# EbookReader_Schematic.net
KiCad netlist of a schematic drawn in EAGLE
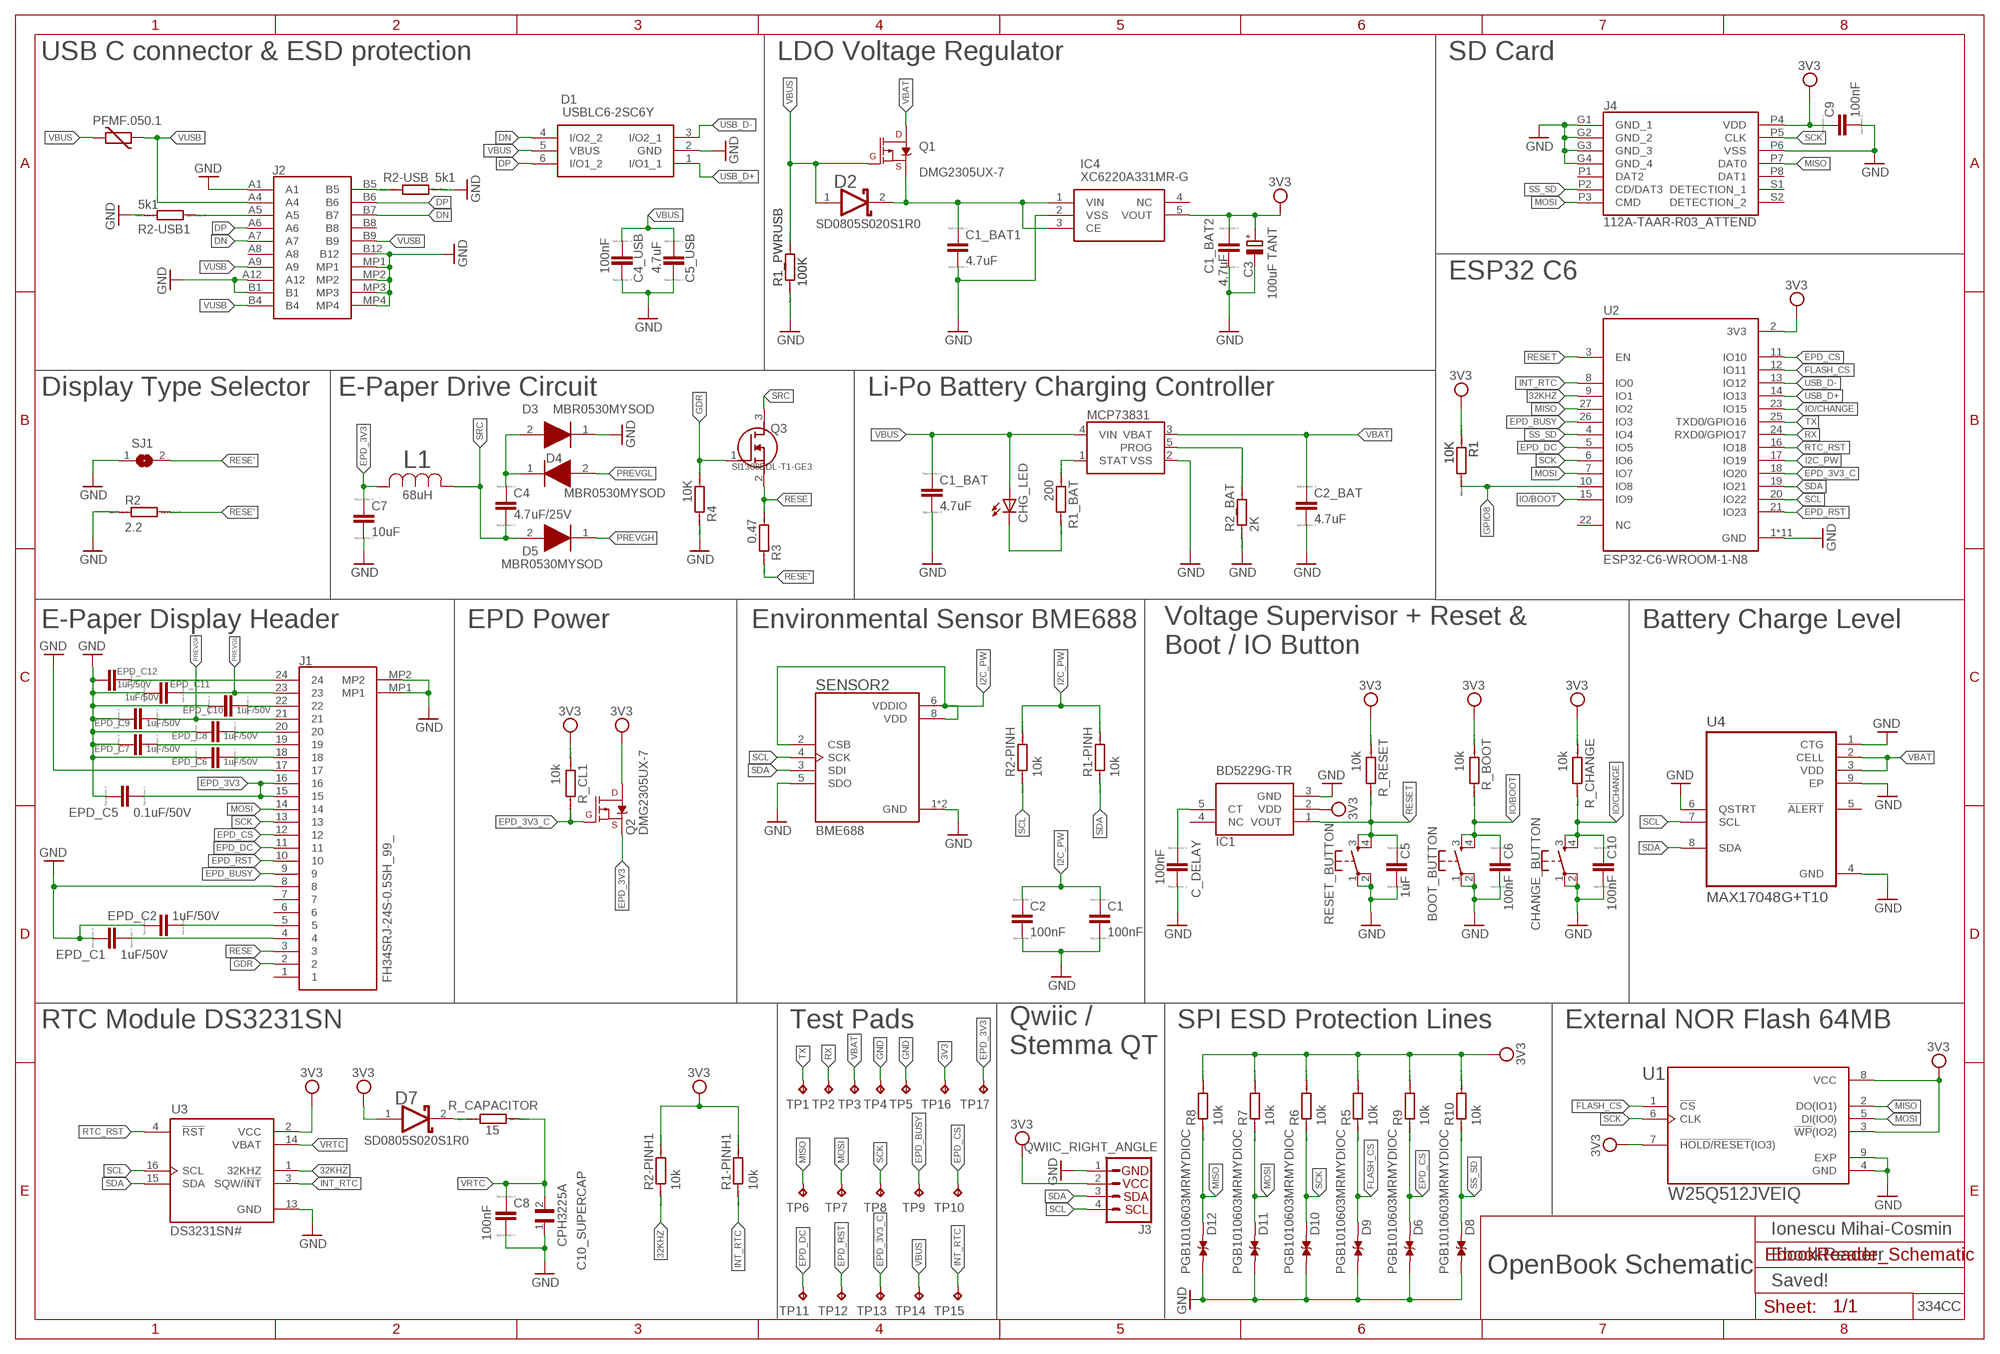
[diagram p0: schematic, sheet 1]

(export (version "E")
  (design (tool "Eeschema 10.0.6"))
  (components
    (comp (ref "BOOT_BUTTON")
      (value "BUTTON_CUSYOMV1FINAL_BUTT")
      (footprint "eagle-import:MYBUTTON")
      (libsource (lib "eagle-import") (part "BUTTON_CUSYOMV1FINAL_BUTT"))
    )
    (comp (ref "C1")
      (value "100nF")
      (footprint "eagle-import:EAGLE-LTSPICE_C0402")
      (libsource (lib "eagle-import") (part "ESP32_WROVER_EAGLE-LTSPICE_C"))
    )
    (comp (ref "C1_BAT")
      (value "4.7uF")
      (footprint "eagle-import:EAGLE-LTSPICE_C0402")
      (libsource (lib "eagle-import") (part "ESP32_WROVER_EAGLE-LTSPICE_C"))
    )
    (comp (ref "C1_BAT1")
      (value "4.7uF")
      (footprint "eagle-import:EAGLE-LTSPICE_C0402")
      (libsource (lib "eagle-import") (part "ESP32_WROVER_EAGLE-LTSPICE_C"))
    )
    (comp (ref "C1_BAT2")
      (value "4.7uF")
      (footprint "eagle-import:EAGLE-LTSPICE_C0402")
      (libsource (lib "eagle-import") (part "ESP32_WROVER_EAGLE-LTSPICE_C"))
    )
    (comp (ref "C2")
      (value "100nF")
      (footprint "eagle-import:EAGLE-LTSPICE_C0402")
      (libsource (lib "eagle-import") (part "ESP32_WROVER_EAGLE-LTSPICE_C"))
    )
    (comp (ref "C2_BAT")
      (value "4.7uF")
      (footprint "eagle-import:EAGLE-LTSPICE_C0402")
      (libsource (lib "eagle-import") (part "ESP32_WROVER_EAGLE-LTSPICE_C"))
    )
    (comp (ref "C3")
      (value "100uF TANT")
      (footprint "eagle-import:RCL_CT3528")
      (libsource (lib "eagle-import") (part "RCL_CPOL-EUCT3528"))
    )
    (comp (ref "C4")
      (value "4.7uF/25V")
      (footprint "eagle-import:EAGLE-LTSPICE_C0402")
      (libsource (lib "eagle-import") (part "ESP32_WROVER_EAGLE-LTSPICE_C"))
    )
    (comp (ref "C4_USB")
      (value "100nF")
      (footprint "eagle-import:EAGLE-LTSPICE_C0402")
      (libsource (lib "eagle-import") (part "ESP32_WROVER_EAGLE-LTSPICE_C"))
    )
    (comp (ref "C5")
      (value "1uF")
      (footprint "eagle-import:EAGLE-LTSPICE_C0402")
      (libsource (lib "eagle-import") (part "ESP32_WROVER_EAGLE-LTSPICE_C"))
    )
    (comp (ref "C5_USB")
      (value "4.7uF")
      (footprint "eagle-import:EAGLE-LTSPICE_C0402")
      (libsource (lib "eagle-import") (part "ESP32_WROVER_EAGLE-LTSPICE_C"))
    )
    (comp (ref "C6")
      (value "100nF")
      (footprint "eagle-import:EAGLE-LTSPICE_C0402")
      (libsource (lib "eagle-import") (part "ESP32_WROVER_EAGLE-LTSPICE_C"))
    )
    (comp (ref "C7")
      (value "10uF")
      (footprint "eagle-import:EAGLE-LTSPICE_C0402")
      (libsource (lib "eagle-import") (part "ESP32_WROVER_EAGLE-LTSPICE_C"))
    )
    (comp (ref "C8")
      (value "100nF")
      (footprint "eagle-import:EAGLE-LTSPICE_C0402")
      (libsource (lib "eagle-import") (part "ESP32_WROVER_EAGLE-LTSPICE_C"))
    )
    (comp (ref "C9")
      (value "100nF")
      (footprint "eagle-import:EAGLE-LTSPICE_C0402")
      (libsource (lib "eagle-import") (part "ESP32_WROVER_EAGLE-LTSPICE_C"))
    )
    (comp (ref "C10")
      (value "100nF")
      (footprint "eagle-import:EAGLE-LTSPICE_C0402")
      (libsource (lib "eagle-import") (part "ESP32_WROVER_EAGLE-LTSPICE_C"))
    )
    (comp (ref "C10_SUPERCAP")
      (value "CPH3225A")
      (footprint "eagle-import:CAPCP3225X100N")
      (fields (field (name "MF") "Seiko Instruments"))
      (libsource (lib "eagle-import") (part "CPH3225A"))
    )
    (comp (ref "CHANGE_BUTTON")
      (value "BUTTON_CUSYOMV1FINAL_BUTT")
      (footprint "eagle-import:MYBUTTON")
      (libsource (lib "eagle-import") (part "BUTTON_CUSYOMV1FINAL_BUTT"))
    )
    (comp (ref "CHG_LED")
      (value "ADAFRUIT_LEDCHIP-LED0603")
      (footprint "eagle-import:ADAFRUIT_CHIP-LED0603")
      (libsource (lib "eagle-import") (part "ADAFRUIT_LEDCHIP-LED0603"))
    )
    (comp (ref "C_DELAY")
      (value "100nF")
      (footprint "eagle-import:EAGLE-LTSPICE_C0402")
      (libsource (lib "eagle-import") (part "ESP32_WROVER_EAGLE-LTSPICE_C"))
    )
    (comp (ref "D1")
      (value "USBLC6-2SC6Y")
      (footprint "eagle-import:SOT95P280X145-6N")
      (fields (field (name "MF") "STMicroelectronics"))
      (libsource (lib "eagle-import") (part "USBLC6-2SC6Y"))
    )
    (comp (ref "D2")
      (value "ESP32_WROVER_AVX---SD0805S020S1R0_AVX_SD0805S020S1R0_0_0")
      (footprint "eagle-import:ESP32_WROVER_AVX---SD0805S020S1R0_AVX_SD0805S020S1R0_0")
      (fields (field (name "FOOPRINT") "SD0805S020S1R0"))
      (libsource (lib "eagle-import") (part "ESP32_WROVER_AVX---SD0805S020S1R0_AVX_SD0805S020S1R0_0_0"))
    )
    (comp (ref "D3")
      (value "MBR0530MYSOD")
      (footprint "eagle-import:SOD3716X135N")
      (libsource (lib "eagle-import") (part "MBR0530MYSOD"))
    )
    (comp (ref "D4")
      (value "MBR0530MYSOD")
      (footprint "eagle-import:SOD3716X135N")
      (libsource (lib "eagle-import") (part "MBR0530MYSOD"))
    )
    (comp (ref "D5")
      (value "MBR0530MYSOD")
      (footprint "eagle-import:SOD3716X135N")
      (libsource (lib "eagle-import") (part "MBR0530MYSOD"))
    )
    (comp (ref "D6")
      (value "PGB1010603MRMYDIOC")
      (footprint "eagle-import:DIOC1608X36N")
      (libsource (lib "eagle-import") (part "PGB1010603MRMYDIOC"))
    )
    (comp (ref "D7")
      (value "ESP32_WROVER_AVX---SD0805S020S1R0_AVX_SD0805S020S1R0_0_0")
      (footprint "eagle-import:ESP32_WROVER_AVX---SD0805S020S1R0_AVX_SD0805S020S1R0_0")
      (fields (field (name "FOOPRINT") "SD0805S020S1R0"))
      (libsource (lib "eagle-import") (part "ESP32_WROVER_AVX---SD0805S020S1R0_AVX_SD0805S020S1R0_0_0"))
    )
    (comp (ref "D8")
      (value "PGB1010603MRMYDIOC")
      (footprint "eagle-import:DIOC1608X36N")
      (libsource (lib "eagle-import") (part "PGB1010603MRMYDIOC"))
    )
    (comp (ref "D9")
      (value "PGB1010603MRMYDIOC")
      (footprint "eagle-import:DIOC1608X36N")
      (libsource (lib "eagle-import") (part "PGB1010603MRMYDIOC"))
    )
    (comp (ref "D10")
      (value "PGB1010603MRMYDIOC")
      (footprint "eagle-import:DIOC1608X36N")
      (libsource (lib "eagle-import") (part "PGB1010603MRMYDIOC"))
    )
    (comp (ref "D11")
      (value "PGB1010603MRMYDIOC")
      (footprint "eagle-import:DIOC1608X36N")
      (libsource (lib "eagle-import") (part "PGB1010603MRMYDIOC"))
    )
    (comp (ref "D12")
      (value "PGB1010603MRMYDIOC")
      (footprint "eagle-import:DIOC1608X36N")
      (libsource (lib "eagle-import") (part "PGB1010603MRMYDIOC"))
    )
    (comp (ref "EPD_C1")
      (value "1uF/50V")
      (footprint "eagle-import:EAGLE-LTSPICE_C0402")
      (libsource (lib "eagle-import") (part "ESP32_WROVER_EAGLE-LTSPICE_C"))
    )
    (comp (ref "EPD_C2")
      (value "1uF/50V")
      (footprint "eagle-import:EAGLE-LTSPICE_C0402")
      (libsource (lib "eagle-import") (part "ESP32_WROVER_EAGLE-LTSPICE_C"))
    )
    (comp (ref "EPD_C5")
      (value "0.1uF/50V")
      (footprint "eagle-import:EAGLE-LTSPICE_C0402")
      (libsource (lib "eagle-import") (part "ESP32_WROVER_EAGLE-LTSPICE_C"))
    )
    (comp (ref "EPD_C6")
      (value "1uF/50V")
      (footprint "eagle-import:EAGLE-LTSPICE_C0402")
      (libsource (lib "eagle-import") (part "ESP32_WROVER_EAGLE-LTSPICE_C"))
    )
    (comp (ref "EPD_C7")
      (value "1uF/50V")
      (footprint "eagle-import:EAGLE-LTSPICE_C0402")
      (libsource (lib "eagle-import") (part "ESP32_WROVER_EAGLE-LTSPICE_C"))
    )
    (comp (ref "EPD_C8")
      (value "1uF/50V")
      (footprint "eagle-import:EAGLE-LTSPICE_C0402")
      (libsource (lib "eagle-import") (part "ESP32_WROVER_EAGLE-LTSPICE_C"))
    )
    (comp (ref "EPD_C9")
      (value "1uF/50V")
      (footprint "eagle-import:EAGLE-LTSPICE_C0402")
      (libsource (lib "eagle-import") (part "ESP32_WROVER_EAGLE-LTSPICE_C"))
    )
    (comp (ref "EPD_C10")
      (value "1uF/50V")
      (footprint "eagle-import:EAGLE-LTSPICE_C0402")
      (libsource (lib "eagle-import") (part "ESP32_WROVER_EAGLE-LTSPICE_C"))
    )
    (comp (ref "EPD_C11")
      (value "1uF/50V")
      (footprint "eagle-import:EAGLE-LTSPICE_C0402")
      (libsource (lib "eagle-import") (part "ESP32_WROVER_EAGLE-LTSPICE_C"))
    )
    (comp (ref "EPD_C12")
      (value "1uF/50V")
      (footprint "eagle-import:EAGLE-LTSPICE_C0402")
      (libsource (lib "eagle-import") (part "ESP32_WROVER_EAGLE-LTSPICE_C"))
    )
    (comp (ref "IC1")
      (value "BD5229G-TR")
      (footprint "eagle-import:SOT95P280X125-5N")
      (fields (field (name "MOUSER_PART_NUMBER") "755-BD5229G-TR"))
      (libsource (lib "eagle-import") (part "BD5229G-TR"))
    )
    (comp (ref "IC4")
      (value "XC6220A331MR-G")
      (footprint "eagle-import:SOT95P280X120-5N")
      (fields (field (name "MOUSER_PART_NUMBER") "865-XC6220A331MR-G"))
      (libsource (lib "eagle-import") (part "XC6220A331MR-G"))
    )
    (comp (ref "J1")
      (value "FH34SRJ-24S-0.5SH_99_")
      (footprint "eagle-import:FH34SRJ24S05SH99")
      (fields
        (field (name "MANUFACTURER_PART_NUMBER") "FH34SRJ-24S-0.5SH(99)")
        (field (name "MOUSER_PART_NUMBER") "798-FH34SRJ24S05SH99")
      )
      (libsource (lib "eagle-import") (part "FH34SRJ-24S-0.5SH_99_"))
    )
    (comp (ref "J2")
      (value "SAMACSYS_PARTS_USB4110-GF-A")
      (footprint "eagle-import:SAMACSYS_PARTS_USB4110GFA")
      (fields
        (field (name "MANUFACTURER_PART_NUMBER") "USB4110-GF-A")
        (field (name "MOUSER_PART_NUMBER") "640-USB4110-GF-A")
      )
      (libsource (lib "eagle-import") (part "SAMACSYS_PARTS_USB4110-GF-A"))
    )
    (comp (ref "J3")
      (value "QWIIC_RIGHT_ANGLE")
      (footprint "eagle-import:JST04_1MM_RA")
      (libsource (lib "eagle-import") (part "QWIIC_CONNECTORJS-1MM"))
    )
    (comp (ref "J4")
      (value "112A-TAAR-R03_ATTEND")
      (footprint "eagle-import:112ATAARR03ATTEND")
      (fields (field (name "MANUFACTURER_PART_NUMBER") "112A-TAAR-R03 ATTEND"))
      (libsource (lib "eagle-import") (part "112A-TAAR-R03_ATTEND"))
    )
    (comp (ref "L1")
      (value "744043680IND_4828-WE-TPC_WRE")
      (footprint "eagle-import:IND_4828-WE-TPC_WRE")
      (fields
        (field (name "MANUFACTURER_PART_NUMBER") "744043680")
        (field (name "VAL") "68uH")
        (field (name "COPYRIGHT") "Copyright (C) 2024 Ultra Librarian. All rights reserved.")
      )
      (libsource (lib "eagle-import") (part "744043680IND_4828-WE-TPC_WRE"))
    )
    (comp (ref "MCP73831")
      (value "ESP32_WROVER_SPARKFUN-IC-POWER_MCP73831")
      (footprint "eagle-import:ESP32_WROVER_SPARKFUN-IC-POWER_SOT23-5")
      (libsource (lib "eagle-import") (part "ESP32_WROVER_SPARKFUN-IC-POWER_MCP73831"))
    )
    (comp (ref "PFMF.050.1")
      (value "ESP32C6_VARISTORCN1812")
      (footprint "eagle-import:ESP32C6_VARISTOR_CT_CN1812")
      (libsource (lib "eagle-import") (part "ESP32C6_VARISTORCN1812"))
    )
    (comp (ref "Q1")
      (value "20V/4.2A/52mΩ/1.4W")
      (footprint "DMG2305UX-7")
      (libsource (lib "eagle-import") (part "ESP32_WROVER_SPARKFUN-DISCRETESEMI_MOSFET_PCH"))
    )
    (comp (ref "Q2")
      (value "20V/4.2A/52mΩ/1.4W")
      (footprint "DMG2305UX-7")
      (libsource (lib "eagle-import") (part "ESP32_WROVER_SPARKFUN-DISCRETESEMI_MOSFET_PCH"))
    )
    (comp (ref "Q3")
      (value "SI1308EDL-T1-GE3")
      (footprint "eagle-import:SOT65P210X110-3N")
      (fields (field (name "MF") "Vishay Siliconix"))
      (libsource (lib "eagle-import") (part "SI1308EDL-T1-GE3"))
    )
    (comp (ref "R1")
      (value "10K")
      (footprint "eagle-import:ESP32_WROVER_EAGLE-LTSPICE_R0402")
      (libsource (lib "eagle-import") (part "ESP32_WROVER_EAGLE-LTSPICE_R"))
    )
    (comp (ref "R1-PINH")
      (value "10k")
      (footprint "eagle-import:ESP32_WROVER_EAGLE-LTSPICE_R0402")
      (libsource (lib "eagle-import") (part "ESP32_WROVER_EAGLE-LTSPICE_R"))
    )
    (comp (ref "R1-PINH1")
      (value "10k")
      (footprint "eagle-import:ESP32_WROVER_EAGLE-LTSPICE_R0402")
      (libsource (lib "eagle-import") (part "ESP32_WROVER_EAGLE-LTSPICE_R"))
    )
    (comp (ref "R1_BAT")
      (value "200")
      (footprint "eagle-import:ESP32_WROVER_EAGLE-LTSPICE_R0402")
      (libsource (lib "eagle-import") (part "ESP32_WROVER_EAGLE-LTSPICE_R"))
    )
    (comp (ref "R1_PWRUSB")
      (value "100K")
      (footprint "eagle-import:ESP32_WROVER_EAGLE-LTSPICE_R0402")
      (libsource (lib "eagle-import") (part "ESP32_WROVER_EAGLE-LTSPICE_R"))
    )
    (comp (ref "R2")
      (value "2.2")
      (footprint "eagle-import:ESP32_WROVER_EAGLE-LTSPICE_R0402")
      (libsource (lib "eagle-import") (part "ESP32_WROVER_EAGLE-LTSPICE_R"))
    )
    (comp (ref "R2-PINH")
      (value "10k")
      (footprint "eagle-import:ESP32_WROVER_EAGLE-LTSPICE_R0402")
      (libsource (lib "eagle-import") (part "ESP32_WROVER_EAGLE-LTSPICE_R"))
    )
    (comp (ref "R2-PINH1")
      (value "10k")
      (footprint "eagle-import:ESP32_WROVER_EAGLE-LTSPICE_R0402")
      (libsource (lib "eagle-import") (part "ESP32_WROVER_EAGLE-LTSPICE_R"))
    )
    (comp (ref "R2-USB")
      (value "5k1")
      (footprint "eagle-import:ESP32_WROVER_EAGLE-LTSPICE_R0402")
      (libsource (lib "eagle-import") (part "ESP32_WROVER_EAGLE-LTSPICE_R"))
    )
    (comp (ref "R2-USB1")
      (value "5k1")
      (footprint "eagle-import:ESP32_WROVER_EAGLE-LTSPICE_R0402")
      (libsource (lib "eagle-import") (part "ESP32_WROVER_EAGLE-LTSPICE_R"))
    )
    (comp (ref "R2_BAT")
      (value "2K")
      (footprint "eagle-import:ESP32_WROVER_EAGLE-LTSPICE_R0402")
      (libsource (lib "eagle-import") (part "ESP32_WROVER_EAGLE-LTSPICE_R"))
    )
    (comp (ref "R3")
      (value "0.47")
      (footprint "eagle-import:ESP32_WROVER_EAGLE-LTSPICE_R0402")
      (libsource (lib "eagle-import") (part "ESP32_WROVER_EAGLE-LTSPICE_R"))
    )
    (comp (ref "R4")
      (value "10K")
      (footprint "eagle-import:ESP32_WROVER_EAGLE-LTSPICE_R0402")
      (libsource (lib "eagle-import") (part "ESP32_WROVER_EAGLE-LTSPICE_R"))
    )
    (comp (ref "R5")
      (value "10k")
      (footprint "eagle-import:ESP32_WROVER_EAGLE-LTSPICE_R0402")
      (libsource (lib "eagle-import") (part "ESP32_WROVER_EAGLE-LTSPICE_R"))
    )
    (comp (ref "R6")
      (value "10k")
      (footprint "eagle-import:ESP32_WROVER_EAGLE-LTSPICE_R0402")
      (libsource (lib "eagle-import") (part "ESP32_WROVER_EAGLE-LTSPICE_R"))
    )
    (comp (ref "R7")
      (value "10k")
      (footprint "eagle-import:ESP32_WROVER_EAGLE-LTSPICE_R0402")
      (libsource (lib "eagle-import") (part "ESP32_WROVER_EAGLE-LTSPICE_R"))
    )
    (comp (ref "R8")
      (value "10k")
      (footprint "eagle-import:ESP32_WROVER_EAGLE-LTSPICE_R0402")
      (libsource (lib "eagle-import") (part "ESP32_WROVER_EAGLE-LTSPICE_R"))
    )
    (comp (ref "R9")
      (value "10k")
      (footprint "eagle-import:ESP32_WROVER_EAGLE-LTSPICE_R0402")
      (libsource (lib "eagle-import") (part "ESP32_WROVER_EAGLE-LTSPICE_R"))
    )
    (comp (ref "R10")
      (value "10k")
      (footprint "eagle-import:ESP32_WROVER_EAGLE-LTSPICE_R0402")
      (libsource (lib "eagle-import") (part "ESP32_WROVER_EAGLE-LTSPICE_R"))
    )
    (comp (ref "RESET_BUTTON")
      (value "BUTTON_CUSYOMV1FINAL_BUTT")
      (footprint "eagle-import:MYBUTTON")
      (libsource (lib "eagle-import") (part "BUTTON_CUSYOMV1FINAL_BUTT"))
    )
    (comp (ref "R_BOOT")
      (value "10k")
      (footprint "eagle-import:ESP32_WROVER_EAGLE-LTSPICE_R0402")
      (libsource (lib "eagle-import") (part "ESP32_WROVER_EAGLE-LTSPICE_R"))
    )
    (comp (ref "R_CAPACITOR")
      (value "15")
      (footprint "eagle-import:ESP32_WROVER_EAGLE-LTSPICE_R0402")
      (libsource (lib "eagle-import") (part "ESP32_WROVER_EAGLE-LTSPICE_R"))
    )
    (comp (ref "R_CHANGE")
      (value "10k")
      (footprint "eagle-import:ESP32_WROVER_EAGLE-LTSPICE_R0402")
      (libsource (lib "eagle-import") (part "ESP32_WROVER_EAGLE-LTSPICE_R"))
    )
    (comp (ref "R_CL1")
      (value "10k")
      (footprint "eagle-import:ESP32_WROVER_EAGLE-LTSPICE_R0402")
      (libsource (lib "eagle-import") (part "ESP32_WROVER_EAGLE-LTSPICE_R"))
    )
    (comp (ref "R_RESET")
      (value "10k")
      (footprint "eagle-import:ESP32_WROVER_EAGLE-LTSPICE_R0402")
      (libsource (lib "eagle-import") (part "ESP32_WROVER_EAGLE-LTSPICE_R"))
    )
    (comp (ref "SENSOR2")
      (value "ESP32_WROVER_BME680_BME680")
      (footprint "BME688")
      (fields (field (name "MF") "Bosch Sensortec") (field (name "MP") "BME680"))
      (libsource (lib "eagle-import") (part "ESP32_WROVER_BME680_BME680"))
    )
    (comp (ref "SJ1") (value "SJ") (footprint "eagle-import:SJ") (libsource (lib "eagle-import") (part "SJ")))
    (comp (ref "TP1")
      (value "TP")
      (footprint "eagle-import:TP20R")
      (libsource (lib "eagle-import") (part "TP"))
    )
    (comp (ref "TP2")
      (value "TP")
      (footprint "eagle-import:TP20R")
      (libsource (lib "eagle-import") (part "TP"))
    )
    (comp (ref "TP3")
      (value "TP")
      (footprint "eagle-import:TP20R")
      (libsource (lib "eagle-import") (part "TP"))
    )
    (comp (ref "TP4")
      (value "TP")
      (footprint "eagle-import:TP20R")
      (libsource (lib "eagle-import") (part "TP"))
    )
    (comp (ref "TP5")
      (value "TP")
      (footprint "eagle-import:TP20R")
      (libsource (lib "eagle-import") (part "TP"))
    )
    (comp (ref "TP6")
      (value "TP")
      (footprint "eagle-import:TP20R")
      (libsource (lib "eagle-import") (part "TP"))
    )
    (comp (ref "TP7")
      (value "TP")
      (footprint "eagle-import:TP20R")
      (libsource (lib "eagle-import") (part "TP"))
    )
    (comp (ref "TP8")
      (value "TP")
      (footprint "eagle-import:TP20R")
      (libsource (lib "eagle-import") (part "TP"))
    )
    (comp (ref "TP9")
      (value "TP")
      (footprint "eagle-import:TP20R")
      (libsource (lib "eagle-import") (part "TP"))
    )
    (comp (ref "TP10")
      (value "TP")
      (footprint "eagle-import:TP20R")
      (libsource (lib "eagle-import") (part "TP"))
    )
    (comp (ref "TP11")
      (value "TP")
      (footprint "eagle-import:TP20R")
      (libsource (lib "eagle-import") (part "TP"))
    )
    (comp (ref "TP12")
      (value "TP")
      (footprint "eagle-import:TP20R")
      (libsource (lib "eagle-import") (part "TP"))
    )
    (comp (ref "TP13")
      (value "TP")
      (footprint "eagle-import:TP20R")
      (libsource (lib "eagle-import") (part "TP"))
    )
    (comp (ref "TP14")
      (value "TP")
      (footprint "eagle-import:TP20R")
      (libsource (lib "eagle-import") (part "TP"))
    )
    (comp (ref "TP15")
      (value "TP")
      (footprint "eagle-import:TP20R")
      (libsource (lib "eagle-import") (part "TP"))
    )
    (comp (ref "TP16")
      (value "TP")
      (footprint "eagle-import:TP20R")
      (libsource (lib "eagle-import") (part "TP"))
    )
    (comp (ref "TP17")
      (value "TP")
      (footprint "eagle-import:TP20R")
      (libsource (lib "eagle-import") (part "TP"))
    )
    (comp (ref "U1")
      (value "W25Q512JVEIQ")
      (footprint "eagle-import:SON127P600X800X80-9N")
      (fields (field (name "MF") "Winbond Electronics"))
      (libsource (lib "eagle-import") (part "W25Q512JVEIQ"))
    )
    (comp (ref "U2")
      (value "ESP32-C6-WROOM-1-N8")
      (footprint "eagle-import:XCVR_ESP32-C6-WROOM-1-N8")
      (fields (field (name "MF") "Espressif Systems"))
      (libsource (lib "eagle-import") (part "ESP32-C6-WROOM-1-N8"))
    )
    (comp (ref "U3")
      (value "DS3231SN#")
      (footprint "eagle-import:SOIC127P1032X265-16N")
      (fields (field (name "MF") "Analog Devices"))
      (libsource (lib "eagle-import") (part "DS3231SN#"))
    )
    (comp (ref "U4")
      (value "MAX17048G+T10")
      (footprint "eagle-import:SON50P200X200X80-9N")
      (fields (field (name "MF") "Analog Devices") (field (name "SPICEPREFIX") "X"))
      (libsource (lib "eagle-import") (part "MAX17048G+T10"))
    )
  )
  (nets
    (net (code "1") (name "3V3") (class "Default")
      (node (ref "C1_BAT2") (pin "1") (pinfunction "1_1") (pintype "passive"))
      (node (ref "C3") (pin "+") (pinfunction "+_+") (pintype "passive"))
      (node (ref "C9") (pin "1") (pinfunction "1_1") (pintype "passive"))
      (node (ref "D7") (pin "1") (pinfunction "ANODE_1") (pintype "bidirectional"))
      (node (ref "IC1") (pin "2") (pinfunction "VDD_2") (pintype "bidirectional"))
      (node (ref "IC4") (pin "5") (pinfunction "VOUT_5") (pintype "bidirectional"))
      (node (ref "J3") (pin "2") (pinfunction "2_2") (pintype "power_in"))
      (node (ref "J4") (pin "P4") (pinfunction "VDD_P4") (pintype "bidirectional"))
      (node (ref "Q2") (pin "1") (pinfunction "D_1") (pintype "bidirectional"))
      (node (ref "R1") (pin "1") (pinfunction "1_1") (pintype "passive"))
      (node (ref "R1-PINH1") (pin "2") (pinfunction "2_2") (pintype "passive"))
      (node (ref "R10") (pin "2") (pinfunction "2_2") (pintype "passive"))
      (node (ref "R2-PINH1") (pin "2") (pinfunction "2_2") (pintype "passive"))
      (node (ref "R5") (pin "2") (pinfunction "2_2") (pintype "passive"))
      (node (ref "R6") (pin "2") (pinfunction "2_2") (pintype "passive"))
      (node (ref "R7") (pin "2") (pinfunction "2_2") (pintype "passive"))
      (node (ref "R8") (pin "2") (pinfunction "2_2") (pintype "passive"))
      (node (ref "R9") (pin "2") (pinfunction "2_2") (pintype "passive"))
      (node (ref "R_BOOT") (pin "1") (pinfunction "1_1") (pintype "passive"))
      (node (ref "R_CHANGE") (pin "1") (pinfunction "1_1") (pintype "passive"))
      (node (ref "R_CL1") (pin "1") (pinfunction "1_1") (pintype "passive"))
      (node (ref "R_RESET") (pin "1") (pinfunction "1_1") (pintype "passive"))
      (node (ref "TP16") (pin "TP") (pinfunction "TP_TP") (pintype "input"))
      (node (ref "U1") (pin "3") (pinfunction "~{WP}(IO2)_3") (pintype "bidirectional"))
      (node (ref "U1") (pin "7") (pinfunction "~{HOLD}/~{RESET}(IO3)_7") (pintype "bidirectional"))
      (node (ref "U1") (pin "8") (pinfunction "VCC_8") (pintype "power_in"))
      (node (ref "U2") (pin "2") (pinfunction "3V3_2") (pintype "power_in"))
      (node (ref "U3") (pin "2") (pinfunction "VCC_2") (pintype "power_in"))
    )
    (net (code "2") (name "32KHZ") (class "Default")
      (node (ref "R2-PINH1") (pin "1") (pinfunction "1_1") (pintype "passive"))
      (node (ref "U2") (pin "9") (pinfunction "IO1_9") (pintype "bidirectional"))
      (node (ref "U3") (pin "1") (pinfunction "32KHZ_1") (pintype "output"))
    )
    (net (code "3") (name "DN") (class "Default")
      (node (ref "D1") (pin "4") (pinfunction "I/O2_2_4") (pintype "bidirectional"))
      (node (ref "J2") (pin "A7") (pinfunction "A7_A7") (pintype "bidirectional"))
      (node (ref "J2") (pin "B7") (pinfunction "B7_B7") (pintype "bidirectional"))
    )
    (net (code "4") (name "DP") (class "Default")
      (node (ref "D1") (pin "6") (pinfunction "I/O1_2_6") (pintype "bidirectional"))
      (node (ref "J2") (pin "A6") (pinfunction "A6_A6") (pintype "bidirectional"))
      (node (ref "J2") (pin "B6") (pinfunction "B6_B6") (pintype "bidirectional"))
    )
    (net (code "5") (name "EPD_3V3") (class "Default")
      (node (ref "C7") (pin "1") (pinfunction "1_1") (pintype "passive"))
      (node (ref "EPD_C5") (pin "1") (pinfunction "1_1") (pintype "passive"))
      (node (ref "J1") (pin "15") (pinfunction "15_15") (pintype "bidirectional"))
      (node (ref "J1") (pin "16") (pinfunction "16_16") (pintype "bidirectional"))
      (node (ref "L1") (pin "2") (pinfunction "2_2") (pintype "passive"))
      (node (ref "Q2") (pin "3") (pinfunction "S_3") (pintype "bidirectional"))
      (node (ref "TP17") (pin "TP") (pinfunction "TP_TP") (pintype "input"))
    )
    (net (code "6") (name "EPD_3V3_C") (class "Default")
      (node (ref "Q2") (pin "2") (pinfunction "G_2") (pintype "bidirectional"))
      (node (ref "R_CL1") (pin "2") (pinfunction "2_2") (pintype "passive"))
      (node (ref "TP13") (pin "TP") (pinfunction "TP_TP") (pintype "input"))
      (node (ref "U2") (pin "18") (pinfunction "IO20_18") (pintype "bidirectional"))
    )
    (net (code "7") (name "EPD_BUSY") (class "Default")
      (node (ref "J1") (pin "9") (pinfunction "9_9") (pintype "bidirectional"))
      (node (ref "TP9") (pin "TP") (pinfunction "TP_TP") (pintype "input"))
      (node (ref "U2") (pin "26") (pinfunction "IO3_26") (pintype "bidirectional"))
    )
    (net (code "8") (name "EPD_CS") (class "Default")
      (node (ref "D6") (pin "2") (pinfunction "2_2") (pintype "passive"))
      (node (ref "J1") (pin "12") (pinfunction "12_12") (pintype "bidirectional"))
      (node (ref "R9") (pin "1") (pinfunction "1_1") (pintype "passive"))
      (node (ref "TP10") (pin "TP") (pinfunction "TP_TP") (pintype "input"))
      (node (ref "U2") (pin "11") (pinfunction "IO10_11") (pintype "bidirectional"))
    )
    (net (code "9") (name "EPD_DC") (class "Default")
      (node (ref "J1") (pin "11") (pinfunction "11_11") (pintype "bidirectional"))
      (node (ref "TP11") (pin "TP") (pinfunction "TP_TP") (pintype "input"))
      (node (ref "U2") (pin "5") (pinfunction "IO5_5") (pintype "bidirectional"))
    )
    (net (code "10") (name "EPD_RST") (class "Default")
      (node (ref "J1") (pin "10") (pinfunction "10_10") (pintype "bidirectional"))
      (node (ref "TP12") (pin "TP") (pinfunction "TP_TP") (pintype "input"))
      (node (ref "U2") (pin "21") (pinfunction "IO23_21") (pintype "bidirectional"))
    )
    (net (code "11") (name "FLASH_CS") (class "Default")
      (node (ref "D9") (pin "2") (pinfunction "2_2") (pintype "passive"))
      (node (ref "R5") (pin "1") (pinfunction "1_1") (pintype "passive"))
      (node (ref "U1") (pin "1") (pinfunction "~{CS}_1") (pintype "input"))
      (node (ref "U2") (pin "12") (pinfunction "IO11_12") (pintype "bidirectional"))
    )
    (net (code "12") (name "GDR") (class "Default")
      (node (ref "J1") (pin "2") (pinfunction "2_2") (pintype "bidirectional"))
      (node (ref "Q3") (pin "1") (pinfunction "G_1") (pintype "bidirectional"))
      (node (ref "R4") (pin "1") (pinfunction "1_1") (pintype "passive"))
    )
    (net (code "13") (name "GND") (class "Default")
      (node (ref "BOOT_BUTTON") (pin "1") (pinfunction "1_1") (pintype "passive"))
      (node (ref "BOOT_BUTTON") (pin "2") (pinfunction "2_2") (pintype "passive"))
      (node (ref "C1") (pin "2") (pinfunction "2_2") (pintype "passive"))
      (node (ref "C10") (pin "2") (pinfunction "2_2") (pintype "passive"))
      (node (ref "C10_SUPERCAP") (pin "1") (pinfunction "1_1") (pintype "passive"))
      (node (ref "C1_BAT") (pin "2") (pinfunction "2_2") (pintype "passive"))
      (node (ref "C1_BAT1") (pin "2") (pinfunction "2_2") (pintype "passive"))
      (node (ref "C1_BAT2") (pin "2") (pinfunction "2_2") (pintype "passive"))
      (node (ref "C2") (pin "2") (pinfunction "2_2") (pintype "passive"))
      (node (ref "C2_BAT") (pin "2") (pinfunction "2_2") (pintype "passive"))
      (node (ref "C3") (pin "-") (pinfunction "-_-") (pintype "passive"))
      (node (ref "C4_USB") (pin "2") (pinfunction "2_2") (pintype "passive"))
      (node (ref "C5") (pin "2") (pinfunction "2_2") (pintype "passive"))
      (node (ref "C5_USB") (pin "2") (pinfunction "2_2") (pintype "passive"))
      (node (ref "C6") (pin "2") (pinfunction "2_2") (pintype "passive"))
      (node (ref "C7") (pin "2") (pinfunction "2_2") (pintype "passive"))
      (node (ref "C8") (pin "2") (pinfunction "2_2") (pintype "passive"))
      (node (ref "C9") (pin "2") (pinfunction "2_2") (pintype "passive"))
      (node (ref "CHANGE_BUTTON") (pin "1") (pinfunction "1_1") (pintype "passive"))
      (node (ref "CHANGE_BUTTON") (pin "2") (pinfunction "2_2") (pintype "passive"))
      (node (ref "C_DELAY") (pin "2") (pinfunction "2_2") (pintype "passive"))
      (node (ref "D1") (pin "2") (pinfunction "GND_2") (pintype "bidirectional"))
      (node (ref "D10") (pin "1") (pinfunction "1_1") (pintype "passive"))
      (node (ref "D11") (pin "1") (pinfunction "1_1") (pintype "passive"))
      (node (ref "D12") (pin "1") (pinfunction "1_1") (pintype "passive"))
      (node (ref "D3") (pin "1") (pinfunction "K_1") (pintype "bidirectional"))
      (node (ref "D6") (pin "1") (pinfunction "1_1") (pintype "passive"))
      (node (ref "D8") (pin "1") (pinfunction "1_1") (pintype "passive"))
      (node (ref "D9") (pin "1") (pinfunction "1_1") (pintype "passive"))
      (node (ref "EPD_C1") (pin "2") (pinfunction "2_2") (pintype "passive"))
      (node (ref "EPD_C10") (pin "2") (pinfunction "2_2") (pintype "passive"))
      (node (ref "EPD_C11") (pin "2") (pinfunction "2_2") (pintype "passive"))
      (node (ref "EPD_C12") (pin "2") (pinfunction "2_2") (pintype "passive"))
      (node (ref "EPD_C2") (pin "2") (pinfunction "2_2") (pintype "passive"))
      (node (ref "EPD_C5") (pin "2") (pinfunction "2_2") (pintype "passive"))
      (node (ref "EPD_C6") (pin "2") (pinfunction "2_2") (pintype "passive"))
      (node (ref "EPD_C7") (pin "2") (pinfunction "2_2") (pintype "passive"))
      (node (ref "EPD_C8") (pin "2") (pinfunction "2_2") (pintype "passive"))
      (node (ref "EPD_C9") (pin "2") (pinfunction "2_2") (pintype "passive"))
      (node (ref "IC1") (pin "3") (pinfunction "GND_3") (pintype "bidirectional"))
      (node (ref "IC4") (pin "2") (pinfunction "VSS_2") (pintype "bidirectional"))
      (node (ref "J1") (pin "17") (pinfunction "17_17") (pintype "bidirectional"))
      (node (ref "J1") (pin "8") (pinfunction "8_8") (pintype "bidirectional"))
      (node (ref "J1") (pin "MP1") (pinfunction "MP1_MP1") (pintype "bidirectional"))
      (node (ref "J1") (pin "MP2") (pinfunction "MP2_MP2") (pintype "bidirectional"))
      (node (ref "J2") (pin "A1") (pinfunction "A1_A1") (pintype "bidirectional"))
      (node (ref "J2") (pin "A12") (pinfunction "A12_A12") (pintype "bidirectional"))
      (node (ref "J2") (pin "B1") (pinfunction "B1_B1") (pintype "bidirectional"))
      (node (ref "J2") (pin "B12") (pinfunction "B12_B12") (pintype "bidirectional"))
      (node (ref "J2") (pin "MP1") (pinfunction "MP1_MP1") (pintype "bidirectional"))
      (node (ref "J2") (pin "MP2") (pinfunction "MP2_MP2") (pintype "bidirectional"))
      (node (ref "J2") (pin "MP3") (pinfunction "MP3_MP3") (pintype "bidirectional"))
      (node (ref "J2") (pin "MP4") (pinfunction "MP4_MP4") (pintype "bidirectional"))
      (node (ref "J3") (pin "1") (pinfunction "1_1") (pintype "power_in"))
      (node (ref "J4") (pin "G1") (pinfunction "GND_1_G1") (pintype "bidirectional"))
      (node (ref "J4") (pin "G2") (pinfunction "GND_2_G2") (pintype "bidirectional"))
      (node (ref "J4") (pin "G3") (pinfunction "GND_3_G3") (pintype "bidirectional"))
      (node (ref "J4") (pin "G4") (pinfunction "GND_4_G4") (pintype "bidirectional"))
      (node (ref "J4") (pin "P6") (pinfunction "VSS_P6") (pintype "bidirectional"))
      (node (ref "MCP73831") (pin "2") (pinfunction "VSS_2") (pintype "power_in"))
      (node (ref "R1_PWRUSB") (pin "1") (pinfunction "1_1") (pintype "passive"))
      (node (ref "R2") (pin "1") (pinfunction "1_1") (pintype "passive"))
      (node (ref "R2-USB") (pin "2") (pinfunction "2_2") (pintype "passive"))
      (node (ref "R2-USB1") (pin "1") (pinfunction "1_1") (pintype "passive"))
      (node (ref "R2_BAT") (pin "1") (pinfunction "1_1") (pintype "passive"))
      (node (ref "R4") (pin "2") (pinfunction "2_2") (pintype "passive"))
      (node (ref "RESET_BUTTON") (pin "1") (pinfunction "1_1") (pintype "passive"))
      (node (ref "RESET_BUTTON") (pin "2") (pinfunction "2_2") (pintype "passive"))
      (node (ref "SENSOR2") (pin "1") (pinfunction "GND_1") (pintype "power_in"))
      (node (ref "SENSOR2") (pin "5") (pinfunction "SDO_5") (pintype "bidirectional"))
      (node (ref "SENSOR2") (pin "7") (pinfunction "GND_7") (pintype "power_in"))
      (node (ref "SJ1") (pin "1") (pinfunction "1_1") (pintype "passive"))
      (node (ref "TP4") (pin "TP") (pinfunction "TP_TP") (pintype "input"))
      (node (ref "TP5") (pin "TP") (pinfunction "TP_TP") (pintype "input"))
      (node (ref "U1") (pin "4") (pinfunction "GND_4") (pintype "power_in"))
      (node (ref "U1") (pin "9") (pinfunction "EXP_9") (pintype "passive"))
      (node (ref "U2") (pin "1") (pinfunction "GND_1") (pintype "power_in"))
      (node (ref "U2") (pin "28") (pinfunction "GND_28") (pintype "power_in"))
      (node (ref "U2") (pin "29_1") (pinfunction "GND_29_1") (pintype "power_in"))
      (node (ref "U2") (pin "29_2") (pinfunction "GND_29_2") (pintype "power_in"))
      (node (ref "U2") (pin "29_3") (pinfunction "GND_29_3") (pintype "power_in"))
      (node (ref "U2") (pin "29_4") (pinfunction "GND_29_4") (pintype "power_in"))
      (node (ref "U2") (pin "29_5") (pinfunction "GND_29_5") (pintype "power_in"))
      (node (ref "U2") (pin "29_6") (pinfunction "GND_29_6") (pintype "power_in"))
      (node (ref "U2") (pin "29_7") (pinfunction "GND_29_7") (pintype "power_in"))
      (node (ref "U2") (pin "29_8") (pinfunction "GND_29_8") (pintype "power_in"))
      (node (ref "U2") (pin "29_9") (pinfunction "GND_29_9") (pintype "power_in"))
      (node (ref "U3") (pin "13") (pinfunction "GND_13") (pintype "power_in"))
      (node (ref "U4") (pin "1") (pinfunction "CTG_1") (pintype "power_in"))
      (node (ref "U4") (pin "4") (pinfunction "GND_4") (pintype "power_in"))
      (node (ref "U4") (pin "6") (pinfunction "QSTRT_6") (pintype "input"))
      (node (ref "U4") (pin "9") (pinfunction "EP_9") (pintype "power_in"))
    )
    (net (code "14") (name "GPIO8") (class "Default")
      (node (ref "R1") (pin "2") (pinfunction "2_2") (pintype "passive"))
      (node (ref "U2") (pin "10") (pinfunction "IO8_10") (pintype "bidirectional"))
    )
    (net (code "15") (name "I2C_PW") (class "Default")
      (node (ref "C1") (pin "1") (pinfunction "1_1") (pintype "passive"))
      (node (ref "C2") (pin "1") (pinfunction "1_1") (pintype "passive"))
      (node (ref "R1-PINH") (pin "2") (pinfunction "2_2") (pintype "passive"))
      (node (ref "R2-PINH") (pin "2") (pinfunction "2_2") (pintype "passive"))
      (node (ref "SENSOR2") (pin "2") (pinfunction "CSB_2") (pintype "input"))
      (node (ref "SENSOR2") (pin "6") (pinfunction "VDDIO_6") (pintype "power_in"))
      (node (ref "SENSOR2") (pin "8") (pinfunction "VDD_8") (pintype "power_in"))
      (node (ref "U2") (pin "17") (pinfunction "IO19_17") (pintype "bidirectional"))
    )
    (net (code "16") (name "INT_RTC") (class "Default")
      (node (ref "R1-PINH1") (pin "1") (pinfunction "1_1") (pintype "passive"))
      (node (ref "TP15") (pin "TP") (pinfunction "TP_TP") (pintype "input"))
      (node (ref "U2") (pin "8") (pinfunction "IO0_8") (pintype "bidirectional"))
      (node (ref "U3") (pin "3") (pinfunction "SQW/~{INT}_3") (pintype "output"))
    )
    (net (code "17") (name "IO{slash}BOOT") (class "Default")
      (node (ref "BOOT_BUTTON") (pin "3") (pinfunction "3_3") (pintype "passive"))
      (node (ref "BOOT_BUTTON") (pin "4") (pinfunction "4_4") (pintype "passive"))
      (node (ref "C6") (pin "1") (pinfunction "1_1") (pintype "passive"))
      (node (ref "R_BOOT") (pin "2") (pinfunction "2_2") (pintype "passive"))
      (node (ref "U2") (pin "15") (pinfunction "IO9_15") (pintype "bidirectional"))
    )
    (net (code "18") (name "IO{slash}CHANGE") (class "Default")
      (node (ref "C10") (pin "1") (pinfunction "1_1") (pintype "passive"))
      (node (ref "CHANGE_BUTTON") (pin "3") (pinfunction "3_3") (pintype "passive"))
      (node (ref "CHANGE_BUTTON") (pin "4") (pinfunction "4_4") (pintype "passive"))
      (node (ref "R_CHANGE") (pin "2") (pinfunction "2_2") (pintype "passive"))
      (node (ref "U2") (pin "23") (pinfunction "IO15_23") (pintype "bidirectional"))
    )
    (net (code "19") (name "MISO") (class "Default")
      (node (ref "D12") (pin "2") (pinfunction "2_2") (pintype "passive"))
      (node (ref "J4") (pin "P7") (pinfunction "DAT0_P7") (pintype "bidirectional"))
      (node (ref "R8") (pin "1") (pinfunction "1_1") (pintype "passive"))
      (node (ref "TP6") (pin "TP") (pinfunction "TP_TP") (pintype "input"))
      (node (ref "U1") (pin "2") (pinfunction "DO(IO1)_2") (pintype "bidirectional"))
      (node (ref "U2") (pin "27") (pinfunction "IO2_27") (pintype "bidirectional"))
    )
    (net (code "20") (name "MOSI") (class "Default")
      (node (ref "D11") (pin "2") (pinfunction "2_2") (pintype "passive"))
      (node (ref "J1") (pin "14") (pinfunction "14_14") (pintype "bidirectional"))
      (node (ref "J4") (pin "P3") (pinfunction "CMD_P3") (pintype "bidirectional"))
      (node (ref "R7") (pin "1") (pinfunction "1_1") (pintype "passive"))
      (node (ref "TP7") (pin "TP") (pinfunction "TP_TP") (pintype "input"))
      (node (ref "U1") (pin "5") (pinfunction "DI(IO0)_5") (pintype "bidirectional"))
      (node (ref "U2") (pin "7") (pinfunction "IO7_7") (pintype "bidirectional"))
    )
    (net (code "21") (name "Net-(CHG_LED-PadC)") (class "Default")
      (node (ref "CHG_LED") (pin "C") (pinfunction "C_C") (pintype "passive"))
      (node (ref "R1_BAT") (pin "2") (pinfunction "2_2") (pintype "passive"))
    )
    (net (code "22") (name "Net-(D2-CATHODE)") (class "Default")
      (node (ref "C1_BAT1") (pin "1") (pinfunction "1_1") (pintype "passive"))
      (node (ref "D2") (pin "2") (pinfunction "CATHODE_2") (pintype "bidirectional"))
      (node (ref "IC4") (pin "1") (pinfunction "VIN_1") (pintype "bidirectional"))
      (node (ref "IC4") (pin "3") (pinfunction "CE_3") (pintype "bidirectional"))
      (node (ref "Q1") (pin "3") (pinfunction "S_3") (pintype "bidirectional"))
    )
    (net (code "23") (name "Net-(D3-A)") (class "Default")
      (node (ref "C4") (pin "1") (pinfunction "1_1") (pintype "passive"))
      (node (ref "D3") (pin "2") (pinfunction "A_2") (pintype "bidirectional"))
      (node (ref "D4") (pin "1") (pinfunction "K_1") (pintype "bidirectional"))
    )
    (net (code "24") (name "Net-(D7-CATHODE)") (class "Default")
      (node (ref "D7") (pin "2") (pinfunction "CATHODE_2") (pintype "bidirectional"))
      (node (ref "R_CAPACITOR") (pin "2") (pinfunction "2_2") (pintype "passive"))
    )
    (net (code "25") (name "Net-(EPD_C1-Pad1)") (class "Default")
      (node (ref "EPD_C1") (pin "1") (pinfunction "1_1") (pintype "passive"))
      (node (ref "J1") (pin "4") (pinfunction "4_4") (pintype "bidirectional"))
    )
    (net (code "26") (name "Net-(EPD_C2-Pad1)") (class "Default")
      (node (ref "EPD_C2") (pin "1") (pinfunction "1_1") (pintype "passive"))
      (node (ref "J1") (pin "5") (pinfunction "5_5") (pintype "bidirectional"))
    )
    (net (code "27") (name "Net-(EPD_C6-Pad1)") (class "Default")
      (node (ref "EPD_C6") (pin "1") (pinfunction "1_1") (pintype "passive"))
      (node (ref "J1") (pin "18") (pinfunction "18_18") (pintype "bidirectional"))
    )
    (net (code "28") (name "Net-(EPD_C7-Pad1)") (class "Default")
      (node (ref "EPD_C7") (pin "1") (pinfunction "1_1") (pintype "passive"))
      (node (ref "J1") (pin "19") (pinfunction "19_19") (pintype "bidirectional"))
    )
    (net (code "29") (name "Net-(EPD_C8-Pad1)") (class "Default")
      (node (ref "EPD_C8") (pin "1") (pinfunction "1_1") (pintype "passive"))
      (node (ref "J1") (pin "20") (pinfunction "20_20") (pintype "bidirectional"))
    )
    (net (code "30") (name "Net-(EPD_C10-Pad1)") (class "Default")
      (node (ref "EPD_C10") (pin "1") (pinfunction "1_1") (pintype "passive"))
      (node (ref "J1") (pin "22") (pinfunction "22_22") (pintype "bidirectional"))
    )
    (net (code "31") (name "Net-(EPD_C12-Pad1)") (class "Default")
      (node (ref "EPD_C12") (pin "1") (pinfunction "1_1") (pintype "passive"))
      (node (ref "J1") (pin "24") (pinfunction "24_24") (pintype "bidirectional"))
    )
    (net (code "32") (name "Net-(IC1-CT)") (class "Default")
      (node (ref "C_DELAY") (pin "1") (pinfunction "1_1") (pintype "passive"))
      (node (ref "IC1") (pin "5") (pinfunction "CT_5") (pintype "bidirectional"))
    )
    (net (code "33") (name "Net-(J2-PadA5)") (class "Default")
      (node (ref "J2") (pin "A5") (pinfunction "A5_A5") (pintype "bidirectional"))
      (node (ref "R2-USB1") (pin "2") (pinfunction "2_2") (pintype "passive"))
    )
    (net (code "34") (name "Net-(J2-PadB5)") (class "Default")
      (node (ref "J2") (pin "B5") (pinfunction "B5_B5") (pintype "bidirectional"))
      (node (ref "R2-USB") (pin "1") (pinfunction "1_1") (pintype "passive"))
    )
    (net (code "35") (name "Net-(MCP73831-PROG)") (class "Default")
      (node (ref "MCP73831") (pin "5") (pinfunction "PROG_5") (pintype "input"))
      (node (ref "R2_BAT") (pin "2") (pinfunction "2_2") (pintype "passive"))
    )
    (net (code "36") (name "Net-(MCP73831-STAT)") (class "Default")
      (node (ref "MCP73831") (pin "1") (pinfunction "STAT_1") (pintype "output"))
      (node (ref "R1_BAT") (pin "1") (pinfunction "1_1") (pintype "passive"))
    )
    (net (code "37") (name "PREVGH") (class "Default")
      (node (ref "D5") (pin "1") (pinfunction "K_1") (pintype "bidirectional"))
      (node (ref "EPD_C9") (pin "1") (pinfunction "1_1") (pintype "passive"))
      (node (ref "J1") (pin "21") (pinfunction "21_21") (pintype "bidirectional"))
    )
    (net (code "38") (name "PREVGL") (class "Default")
      (node (ref "D4") (pin "2") (pinfunction "A_2") (pintype "bidirectional"))
      (node (ref "EPD_C11") (pin "1") (pinfunction "1_1") (pintype "passive"))
      (node (ref "J1") (pin "23") (pinfunction "23_23") (pintype "bidirectional"))
    )
    (net (code "39") (name "RESE") (class "Default")
      (node (ref "J1") (pin "3") (pinfunction "3_3") (pintype "bidirectional"))
      (node (ref "Q3") (pin "2") (pinfunction "S_2") (pintype "bidirectional"))
      (node (ref "R3") (pin "1") (pinfunction "1_1") (pintype "passive"))
    )
    (net (code "40") (name "RESE'") (class "Default")
      (node (ref "R2") (pin "2") (pinfunction "2_2") (pintype "passive"))
      (node (ref "R3") (pin "2") (pinfunction "2_2") (pintype "passive"))
      (node (ref "SJ1") (pin "2") (pinfunction "2_2") (pintype "passive"))
    )
    (net (code "41") (name "RESET") (class "Default")
      (node (ref "C5") (pin "1") (pinfunction "1_1") (pintype "passive"))
      (node (ref "IC1") (pin "1") (pinfunction "VOUT_1") (pintype "bidirectional"))
      (node (ref "RESET_BUTTON") (pin "3") (pinfunction "3_3") (pintype "passive"))
      (node (ref "RESET_BUTTON") (pin "4") (pinfunction "4_4") (pintype "passive"))
      (node (ref "R_RESET") (pin "2") (pinfunction "2_2") (pintype "passive"))
      (node (ref "U2") (pin "3") (pinfunction "EN_3") (pintype "input"))
    )
    (net (code "42") (name "RTC_RST") (class "Default")
      (node (ref "U2") (pin "16") (pinfunction "IO18_16") (pintype "bidirectional"))
      (node (ref "U3") (pin "4") (pinfunction "~{RST}_4") (pintype "input"))
    )
    (net (code "43") (name "RX") (class "Default")
      (node (ref "TP2") (pin "TP") (pinfunction "TP_TP") (pintype "input"))
      (node (ref "U2") (pin "24") (pinfunction "RXD0/GPIO17_24") (pintype "bidirectional"))
    )
    (net (code "44") (name "SCK") (class "Default")
      (node (ref "D10") (pin "2") (pinfunction "2_2") (pintype "passive"))
      (node (ref "J1") (pin "13") (pinfunction "13_13") (pintype "bidirectional"))
      (node (ref "J4") (pin "P5") (pinfunction "CLK_P5") (pintype "bidirectional"))
      (node (ref "R6") (pin "1") (pinfunction "1_1") (pintype "passive"))
      (node (ref "TP8") (pin "TP") (pinfunction "TP_TP") (pintype "input"))
      (node (ref "U1") (pin "6") (pinfunction "CLK_6") (pintype "input"))
      (node (ref "U2") (pin "6") (pinfunction "IO6_6") (pintype "bidirectional"))
    )
    (net (code "45") (name "SCL") (class "Default")
      (node (ref "J3") (pin "4") (pinfunction "4_4") (pintype "passive"))
      (node (ref "R2-PINH") (pin "1") (pinfunction "1_1") (pintype "passive"))
      (node (ref "SENSOR2") (pin "4") (pinfunction "SCK_4") (pintype "input"))
      (node (ref "U2") (pin "20") (pinfunction "IO22_20") (pintype "bidirectional"))
      (node (ref "U3") (pin "16") (pinfunction "SCL_16") (pintype "input"))
      (node (ref "U4") (pin "7") (pinfunction "SCL_7") (pintype "input"))
    )
    (net (code "46") (name "SDA") (class "Default")
      (node (ref "J3") (pin "3") (pinfunction "3_3") (pintype "passive"))
      (node (ref "R1-PINH") (pin "1") (pinfunction "1_1") (pintype "passive"))
      (node (ref "SENSOR2") (pin "3") (pinfunction "SDI_3") (pintype "bidirectional"))
      (node (ref "U2") (pin "19") (pinfunction "IO21_19") (pintype "bidirectional"))
      (node (ref "U3") (pin "15") (pinfunction "SDA_15") (pintype "bidirectional"))
      (node (ref "U4") (pin "8") (pinfunction "SDA_8") (pintype "bidirectional"))
    )
    (net (code "47") (name "SRC") (class "Default")
      (node (ref "C4") (pin "2") (pinfunction "2_2") (pintype "passive"))
      (node (ref "D5") (pin "2") (pinfunction "A_2") (pintype "bidirectional"))
      (node (ref "L1") (pin "1") (pinfunction "1_1") (pintype "passive"))
      (node (ref "Q3") (pin "3") (pinfunction "D_3") (pintype "bidirectional"))
    )
    (net (code "48") (name "SS_SD") (class "Default")
      (node (ref "D8") (pin "2") (pinfunction "2_2") (pintype "passive"))
      (node (ref "J4") (pin "P2") (pinfunction "CD/DAT3_P2") (pintype "bidirectional"))
      (node (ref "R10") (pin "1") (pinfunction "1_1") (pintype "passive"))
      (node (ref "U2") (pin "4") (pinfunction "IO4_4") (pintype "bidirectional"))
    )
    (net (code "49") (name "TX") (class "Default")
      (node (ref "TP1") (pin "TP") (pinfunction "TP_TP") (pintype "input"))
      (node (ref "U2") (pin "25") (pinfunction "TXD0/GPIO16_25") (pintype "bidirectional"))
    )
    (net (code "50") (name "USB_D+") (class "Default")
      (node (ref "D1") (pin "1") (pinfunction "I/O1_1_1") (pintype "bidirectional"))
      (node (ref "U2") (pin "14") (pinfunction "IO13_14") (pintype "bidirectional"))
    )
    (net (code "51") (name "USB_D-") (class "Default")
      (node (ref "D1") (pin "3") (pinfunction "I/O2_1_3") (pintype "bidirectional"))
      (node (ref "U2") (pin "13") (pinfunction "IO12_13") (pintype "bidirectional"))
    )
    (net (code "52") (name "VBAT") (class "Default")
      (node (ref "C2_BAT") (pin "1") (pinfunction "1_1") (pintype "passive"))
      (node (ref "MCP73831") (pin "3") (pinfunction "VBAT_3") (pintype "power_in"))
      (node (ref "Q1") (pin "1") (pinfunction "D_1") (pintype "bidirectional"))
      (node (ref "TP3") (pin "TP") (pinfunction "TP_TP") (pintype "input"))
      (node (ref "U4") (pin "2") (pinfunction "CELL_2") (pintype "power_in"))
      (node (ref "U4") (pin "3") (pinfunction "VDD_3") (pintype "power_in"))
    )
    (net (code "53") (name "VBUS") (class "Default")
      (node (ref "C1_BAT") (pin "1") (pinfunction "1_1") (pintype "passive"))
      (node (ref "C4_USB") (pin "1") (pinfunction "1_1") (pintype "passive"))
      (node (ref "C5_USB") (pin "1") (pinfunction "1_1") (pintype "passive"))
      (node (ref "CHG_LED") (pin "A") (pinfunction "A_A") (pintype "passive"))
      (node (ref "D1") (pin "5") (pinfunction "VBUS_5") (pintype "bidirectional"))
      (node (ref "D2") (pin "1") (pinfunction "ANODE_1") (pintype "bidirectional"))
      (node (ref "MCP73831") (pin "4") (pinfunction "VIN_4") (pintype "power_in"))
      (node (ref "PFMF.050.1") (pin "2") (pinfunction "2_2") (pintype "passive"))
      (node (ref "Q1") (pin "2") (pinfunction "G_2") (pintype "bidirectional"))
      (node (ref "R1_PWRUSB") (pin "2") (pinfunction "2_2") (pintype "passive"))
      (node (ref "TP14") (pin "TP") (pinfunction "TP_TP") (pintype "input"))
    )
    (net (code "54") (name "VRTC") (class "Default")
      (node (ref "C10_SUPERCAP") (pin "2") (pinfunction "2_2") (pintype "passive"))
      (node (ref "C8") (pin "1") (pinfunction "1_1") (pintype "passive"))
      (node (ref "R_CAPACITOR") (pin "1") (pinfunction "1_1") (pintype "passive"))
      (node (ref "U3") (pin "14") (pinfunction "VBAT_14") (pintype "power_in"))
    )
    (net (code "55") (name "VUSB") (class "Default")
      (node (ref "J2") (pin "A4") (pinfunction "A4_A4") (pintype "bidirectional"))
      (node (ref "J2") (pin "A9") (pinfunction "A9_A9") (pintype "bidirectional"))
      (node (ref "J2") (pin "B4") (pinfunction "B4_B4") (pintype "bidirectional"))
      (node (ref "J2") (pin "B9") (pinfunction "B9_B9") (pintype "bidirectional"))
      (node (ref "PFMF.050.1") (pin "1") (pinfunction "1_1") (pintype "passive"))
    )
    (net (code "56") (name "unconnected-(IC1-NC-Pad4)") (class "Default")
      (node (ref "IC1") (pin "4") (pinfunction "NC_4") (pintype "no_connect"))
    )
    (net (code "57") (name "unconnected-(IC4-NC-Pad4)") (class "Default")
      (node (ref "IC4") (pin "4") (pinfunction "NC_4") (pintype "no_connect"))
    )
    (net (code "58") (name "unconnected-(J1-Pad1)") (class "Default")
      (node (ref "J1") (pin "1") (pinfunction "1_1") (pintype "bidirectional"))
    )
    (net (code "59") (name "unconnected-(J1-Pad6)") (class "Default")
      (node (ref "J1") (pin "6") (pinfunction "6_6") (pintype "bidirectional"))
    )
    (net (code "60") (name "unconnected-(J1-Pad7)") (class "Default")
      (node (ref "J1") (pin "7") (pinfunction "7_7") (pintype "bidirectional"))
    )
    (net (code "61") (name "unconnected-(J2-PadA8)") (class "Default")
      (node (ref "J2") (pin "A8") (pinfunction "A8_A8") (pintype "bidirectional"))
    )
    (net (code "62") (name "unconnected-(J2-PadB8)") (class "Default")
      (node (ref "J2") (pin "B8") (pinfunction "B8_B8") (pintype "bidirectional"))
    )
    (net (code "63") (name "unconnected-(J4-DAT1-PadP8)") (class "Default")
      (node (ref "J4") (pin "P8") (pinfunction "DAT1_P8") (pintype "bidirectional"))
    )
    (net (code "64") (name "unconnected-(J4-DAT2-PadP1)") (class "Default")
      (node (ref "J4") (pin "P1") (pinfunction "DAT2_P1") (pintype "bidirectional"))
    )
    (net (code "65") (name "unconnected-(J4-DETECTION_1-PadS1)") (class "Default")
      (node (ref "J4") (pin "S1") (pinfunction "DETECTION_1_S1") (pintype "bidirectional"))
    )
    (net (code "66") (name "unconnected-(J4-DETECTION_2-PadS2)") (class "Default")
      (node (ref "J4") (pin "S2") (pinfunction "DETECTION_2_S2") (pintype "bidirectional"))
    )
    (net (code "67") (name "unconnected-(U2-NC-Pad22)") (class "Default")
      (node (ref "U2") (pin "22") (pinfunction "NC_22") (pintype "no_connect"))
    )
    (net (code "68") (name "unconnected-(U4-~{ALERT}-Pad5)") (class "Default")
      (node (ref "U4") (pin "5") (pinfunction "~{ALERT}_5") (pintype "output"))
    )
  )
)
